# Console_Main_Ctl_Board_v2.net
KiCad netlist of a schematic drawn in EAGLE
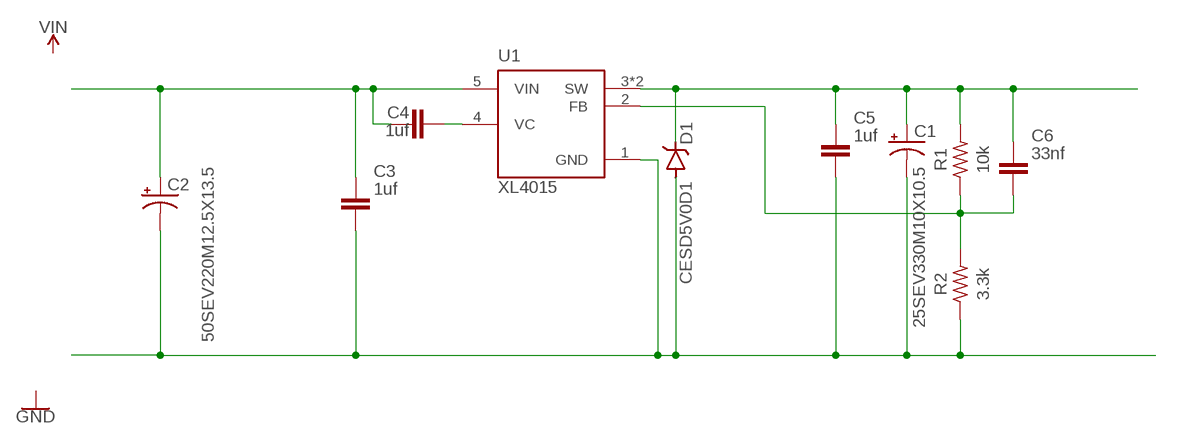
[diagram p0: schematic, sheet 1]

(export (version "E")
  (design (tool "Eeschema 10.0.6"))
  (components
    (comp (ref "C1")
      (value "25SEV330M10X10.5")
      (footprint "eagle-import:CAP_J-V_10X10P5_RUB")
      (fields (field (name "COPYRIGHT") "Copyright (C) 2021 Ultra Librarian. All rights reserved."))
      (libsource (lib "eagle-import") (part "25SEV330M10X10.5"))
    )
    (comp (ref "C2")
      (value "50SEV220M12.5X13.5")
      (footprint "eagle-import:CAP_S-V_12P5X13P5_RUB")
      (fields (field (name "COPYRIGHT") "Copyright (C) 2021 Ultra Librarian. All rights reserved."))
      (libsource (lib "eagle-import") (part "50SEV220M12.5X13.5"))
    )
    (comp (ref "C3")
      (value "1uf")
      (footprint "eagle-import:CAPC3216X135")
      (libsource (lib "eagle-import") (part "CCHIP-1206(3216-METRIC)_"))
    )
    (comp (ref "C4")
      (value "1uf")
      (footprint "eagle-import:CAPC3216X135")
      (libsource (lib "eagle-import") (part "CCHIP-1206(3216-METRIC)_"))
    )
    (comp (ref "C5")
      (value "1uf")
      (footprint "eagle-import:CAPC3216X135")
      (libsource (lib "eagle-import") (part "CCHIP-1206(3216-METRIC)_"))
    )
    (comp (ref "C6")
      (value "33nf")
      (footprint "eagle-import:CAPC3216X135")
      (libsource (lib "eagle-import") (part "CCHIP-1206(3216-METRIC)_"))
    )
    (comp (ref "D1")
      (value "CESD5V0D1")
      (footprint "eagle-import:SOD-123")
      (fields (field (name "MANUFACTURER") "JCET") (field (name "CREATED_BY") "PCBLayout.com"))
      (libsource (lib "eagle-import") (part "CESD5V0D1"))
    )
    (comp (ref "R1")
      (value "10k")
      (footprint "eagle-import:RESC3216X70")
      (libsource (lib "eagle-import") (part "R-USCHIP-1206(3216-METRIC)_"))
    )
    (comp (ref "R2")
      (value "3.3k")
      (footprint "eagle-import:RESC3216X70")
      (libsource (lib "eagle-import") (part "R-USCHIP-1206(3216-METRIC)_"))
    )
    (comp (ref "U1")
      (value "XL4015")
      (footprint "eagle-import:CONV_XL4015")
      (fields (field (name "MF") "XLSEMI"))
      (libsource (lib "eagle-import") (part "XL4015"))
    )
  )
  (nets
    (net (code "2") (name "Net-(C1-+)") (class "Default")
      (node (ref "C1") (pin "1") (pinfunction "+_1") (pintype "passive"))
      (node (ref "C5") (pin "1") (pinfunction "1_1") (pintype "passive"))
      (node (ref "C6") (pin "1") (pinfunction "1_1") (pintype "passive"))
      (node (ref "D1") (pin "C") (pinfunction "C_C") (pintype "passive"))
      (node (ref "R1") (pin "2") (pinfunction "2_2") (pintype "passive"))
      (node (ref "U1") (pin "3") (pinfunction "SW_3") (pintype "output"))
      (node (ref "U1") (pin "3.1") (pinfunction "SW_3.1") (pintype "output"))
    )
    (net (code "3") (name "Net-(C1--)") (class "Default")
      (node (ref "C1") (pin "2") (pinfunction "-_2") (pintype "passive"))
      (node (ref "C2") (pin "2") (pinfunction "-_2") (pintype "passive"))
      (node (ref "C3") (pin "2") (pinfunction "2_2") (pintype "passive"))
      (node (ref "C5") (pin "2") (pinfunction "2_2") (pintype "passive"))
      (node (ref "D1") (pin "A") (pinfunction "A_A") (pintype "passive"))
      (node (ref "R2") (pin "1") (pinfunction "1_1") (pintype "passive"))
      (node (ref "U1") (pin "1") (pinfunction "GND_1") (pintype "power_in"))
    )
    (net (code "4") (name "Net-(C2-+)") (class "Default")
      (node (ref "C2") (pin "1") (pinfunction "+_1") (pintype "passive"))
      (node (ref "C3") (pin "1") (pinfunction "1_1") (pintype "passive"))
      (node (ref "C4") (pin "1") (pinfunction "1_1") (pintype "passive"))
      (node (ref "U1") (pin "5") (pinfunction "VIN_5") (pintype "input"))
    )
    (net (code "5") (name "Net-(U1-FB)") (class "Default")
      (node (ref "C6") (pin "2") (pinfunction "2_2") (pintype "passive"))
      (node (ref "R1") (pin "1") (pinfunction "1_1") (pintype "passive"))
      (node (ref "R2") (pin "2") (pinfunction "2_2") (pintype "passive"))
      (node (ref "U1") (pin "2") (pinfunction "FB_2") (pintype "input"))
    )
    (net (code "6") (name "Net-(U1-VC)") (class "Default")
      (node (ref "C4") (pin "2") (pinfunction "2_2") (pintype "passive"))
      (node (ref "U1") (pin "4") (pinfunction "VC_4") (pintype "passive"))
    )
  )
)
